# LightGateBoard.net
KiCad netlist of a schematic drawn in EAGLE
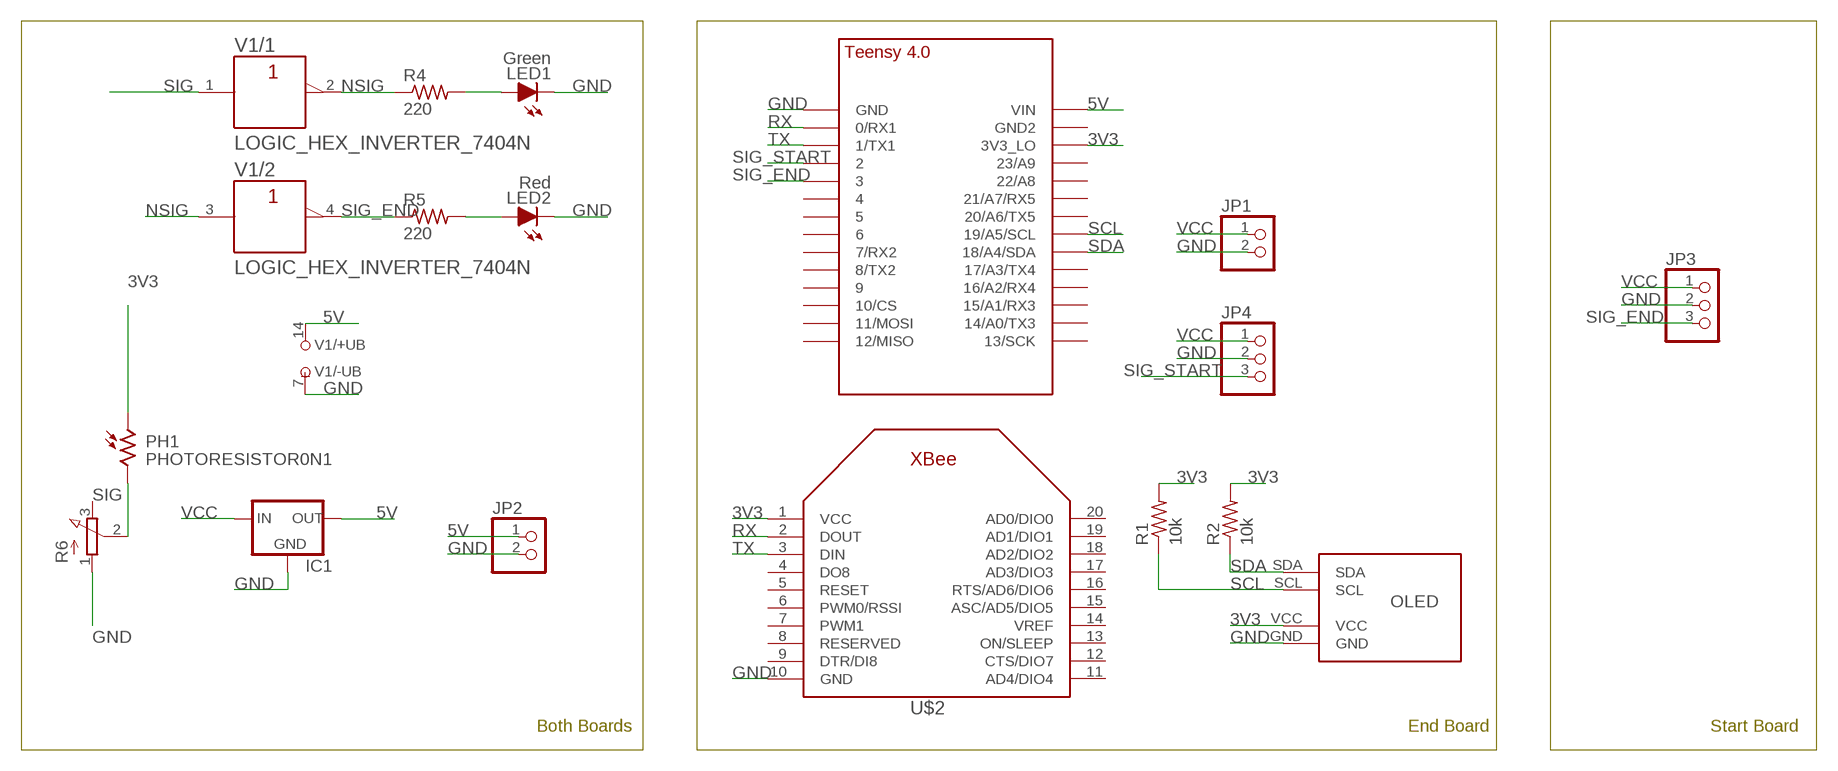
[diagram p0: schematic, sheet 1]

(export (version "E")
  (design (tool "Eeschema 10.0.6"))
  (components
    (comp (ref "IC1")
      (value "REG_5V_L7805_HOR")
      (footprint "eagle-import:TO-220-H")
      (libsource (lib "eagle-import") (part "REG_5V_L7805_HOR"))
    )
    (comp (ref "JP1")
      (value "PINHD-1X2")
      (footprint "eagle-import:1X02")
      (libsource (lib "eagle-import") (part "PINHD-1X2"))
    )
    (comp (ref "JP2")
      (value "PINHD-1X2")
      (footprint "eagle-import:1X02")
      (libsource (lib "eagle-import") (part "PINHD-1X2"))
    )
    (comp (ref "JP3")
      (value "PINHD-1X3")
      (footprint "eagle-import:1X03")
      (libsource (lib "eagle-import") (part "PINHD-1X3"))
    )
    (comp (ref "JP4")
      (value "PINHD-1X3")
      (footprint "eagle-import:1X03")
      (libsource (lib "eagle-import") (part "PINHD-1X3"))
    )
    (comp (ref "LED1")
      (value "Green")
      (footprint "eagle-import:LED-5MM")
      (libsource (lib "eagle-import") (part "LED-5MM"))
    )
    (comp (ref "LED2")
      (value "Red")
      (footprint "eagle-import:LED-5MM")
      (libsource (lib "eagle-import") (part "LED-5MM"))
    )
    (comp (ref "PH1")
      (value "PHOTORESISTOR0N1")
      (footprint "eagle-import:TO46-VT200")
      (libsource (lib "eagle-import") (part "PHOTORESISTOR0N1"))
    )
    (comp (ref "R1")
      (value "10k")
      (footprint "eagle-import:1_4W-0.3")
      (libsource (lib "eagle-import") (part "RES_AXIAL1/4W-0.3"))
    )
    (comp (ref "R2")
      (value "10k")
      (footprint "eagle-import:1_4W-0.3")
      (libsource (lib "eagle-import") (part "RES_AXIAL1/4W-0.3"))
    )
    (comp (ref "R4")
      (value "220")
      (footprint "eagle-import:1_4W-0.3")
      (libsource (lib "eagle-import") (part "RES_AXIAL1/4W-0.3"))
    )
    (comp (ref "R5")
      (value "220")
      (footprint "eagle-import:1_4W-0.3")
      (libsource (lib "eagle-import") (part "RES_AXIAL1/4W-0.3"))
    )
    (comp (ref "R6")
      (value "POTENTIOMETER")
      (footprint "eagle-import:3RP_1610N")
      (libsource (lib "eagle-import") (part "POTENTIOMETER"))
    )
    (comp (ref "U$1")
      (value "TEENSY_4.0_SIMPLE")
      (footprint "eagle-import:TEENSY_4.0_SIMPLE")
      (libsource (lib "eagle-import") (part "TEENSY_4.0_SIMPLE"))
    )
    (comp (ref "U$2")
      (value "XBEE")
      (footprint "eagle-import:XBEE")
      (libsource (lib "eagle-import") (part "XBEE"))
    )
    (comp (ref "U$3")
      (value "OLED_SSD1306")
      (footprint "eagle-import:OLED_SSD1306")
      (libsource (lib "eagle-import") (part "OLED_SSD1306"))
    )
    (comp (ref "V1")
      (value "LOGIC_HEX_INVERTER_7404N")
      (footprint "eagle-import:DIL14")
      (libsource (lib "eagle-import") (part "LOGIC_HEX_INVERTER_7404N"))
    )
  )
  (nets
    (net (code "1") (name "/3V3") (class "Default")
      (node (ref "PH1") (pin "1") (pinfunction "1_1") (pintype "passive"))
      (node (ref "R1") (pin "2") (pinfunction "2_2") (pintype "passive"))
      (node (ref "R2") (pin "2") (pinfunction "2_2") (pintype "passive"))
      (node (ref "U$1") (pin "3V3_LO") (pinfunction "3V3_LO_3V3_LO") (pintype "bidirectional"))
      (node (ref "U$2") (pin "1") (pinfunction "VCC_1") (pintype "power_in"))
      (node (ref "U$3") (pin "VCC") (pinfunction "VCC_VCC") (pintype "bidirectional"))
    )
    (net (code "2") (name "/5V") (class "Default")
      (node (ref "IC1") (pin "3") (pinfunction "OUT_3") (pintype "output"))
      (node (ref "JP2") (pin "1") (pinfunction "1_1") (pintype "passive"))
      (node (ref "U$1") (pin "VIN") (pinfunction "VIN_VIN") (pintype "bidirectional"))
      (node (ref "V1") (pin "14") (pinfunction "+UB_14") (pintype "power_in"))
    )
    (net (code "3") (name "/GND") (class "Default")
      (node (ref "IC1") (pin "2") (pinfunction "GND_2") (pintype "input"))
      (node (ref "JP1") (pin "2") (pinfunction "2_2") (pintype "passive"))
      (node (ref "JP2") (pin "2") (pinfunction "2_2") (pintype "passive"))
      (node (ref "JP3") (pin "2") (pinfunction "2_2") (pintype "passive"))
      (node (ref "JP4") (pin "2") (pinfunction "2_2") (pintype "passive"))
      (node (ref "LED1") (pin "K") (pinfunction "C_K") (pintype "passive"))
      (node (ref "LED2") (pin "K") (pinfunction "C_K") (pintype "passive"))
      (node (ref "R6") (pin "1") (pinfunction "A_1") (pintype "passive"))
      (node (ref "U$1") (pin "GND") (pinfunction "GND_GND") (pintype "bidirectional"))
      (node (ref "U$2") (pin "10") (pinfunction "GND_10") (pintype "power_in"))
      (node (ref "U$3") (pin "GND") (pinfunction "GND_GND") (pintype "bidirectional"))
      (node (ref "V1") (pin "7") (pinfunction "-UB_7") (pintype "power_in"))
    )
    (net (code "4") (name "/NSIG") (class "Default")
      (node (ref "R4") (pin "1") (pinfunction "1_1") (pintype "passive"))
      (node (ref "V1") (pin "2") (pinfunction "Y_2") (pintype "output"))
      (node (ref "V1") (pin "3") (pinfunction "A_3") (pintype "input"))
    )
    (net (code "5") (name "/RX") (class "Default")
      (node (ref "U$1") (pin "0/RX") (pinfunction "0/RX1_0/RX") (pintype "bidirectional"))
      (node (ref "U$2") (pin "2") (pinfunction "DOUT_2") (pintype "output"))
    )
    (net (code "6") (name "/SCL") (class "Default")
      (node (ref "R1") (pin "1") (pinfunction "1_1") (pintype "passive"))
      (node (ref "U$1") (pin "19/A5/SCL") (pinfunction "19/A5/SCL_19/A5/SCL") (pintype "bidirectional"))
      (node (ref "U$3") (pin "SCL") (pinfunction "SCL_SCL") (pintype "bidirectional"))
    )
    (net (code "7") (name "/SDA") (class "Default")
      (node (ref "R2") (pin "1") (pinfunction "1_1") (pintype "passive"))
      (node (ref "U$1") (pin "18/A4/SDA") (pinfunction "18/A4/SDA_18/A4/SDA") (pintype "bidirectional"))
      (node (ref "U$3") (pin "SDA") (pinfunction "SDA_SDA") (pintype "bidirectional"))
    )
    (net (code "8") (name "/SIG") (class "Default")
      (node (ref "PH1") (pin "2") (pinfunction "2_2") (pintype "passive"))
      (node (ref "R6") (pin "2") (pinfunction "S_2") (pintype "passive"))
      (node (ref "V1") (pin "1") (pinfunction "A_1") (pintype "input"))
    )
    (net (code "9") (name "/SIG_END") (class "Default")
      (node (ref "JP3") (pin "3") (pinfunction "3_3") (pintype "passive"))
      (node (ref "R5") (pin "1") (pinfunction "1_1") (pintype "passive"))
      (node (ref "U$1") (pin "3/CANTX") (pinfunction "3_3/CANTX") (pintype "bidirectional"))
      (node (ref "V1") (pin "4") (pinfunction "Y_4") (pintype "output"))
    )
    (net (code "10") (name "/SIG_START") (class "Default")
      (node (ref "JP4") (pin "3") (pinfunction "3_3") (pintype "passive"))
      (node (ref "U$1") (pin "2") (pinfunction "2_2") (pintype "bidirectional"))
    )
    (net (code "11") (name "/TX") (class "Default")
      (node (ref "U$1") (pin "1/TX") (pinfunction "1/TX1_1/TX") (pintype "bidirectional"))
      (node (ref "U$2") (pin "3") (pinfunction "DIN_3") (pintype "input"))
    )
    (net (code "12") (name "/VCC") (class "Default")
      (node (ref "IC1") (pin "1") (pinfunction "IN_1") (pintype "input"))
      (node (ref "JP1") (pin "1") (pinfunction "1_1") (pintype "passive"))
      (node (ref "JP3") (pin "1") (pinfunction "1_1") (pintype "passive"))
      (node (ref "JP4") (pin "1") (pinfunction "1_1") (pintype "passive"))
    )
    (net (code "13") (name "Net-(LED1-PadA)") (class "Default")
      (node (ref "LED1") (pin "A") (pinfunction "A_A") (pintype "passive"))
      (node (ref "R4") (pin "2") (pinfunction "2_2") (pintype "passive"))
    )
    (net (code "14") (name "Net-(LED2-PadA)") (class "Default")
      (node (ref "LED2") (pin "A") (pinfunction "A_A") (pintype "passive"))
      (node (ref "R5") (pin "2") (pinfunction "2_2") (pintype "passive"))
    )
    (net (code "15") (name "unconnected-(R6-E-Pad3)") (class "Default")
      (node (ref "R6") (pin "3") (pinfunction "E_3") (pintype "passive"))
    )
    (net (code "16") (name "unconnected-(U$1-4-Pad4{slash}CANRX)") (class "Default")
      (node (ref "U$1") (pin "4/CANRX") (pinfunction "4_4/CANRX") (pintype "bidirectional"))
    )
    (net (code "17") (name "unconnected-(U$1-7{slash}RX2-Pad7)") (class "Default")
      (node (ref "U$1") (pin "7") (pinfunction "7/RX2_7") (pintype "bidirectional"))
    )
    (net (code "18") (name "unconnected-(U$1-8{slash}TX2-Pad8)") (class "Default")
      (node (ref "U$1") (pin "8") (pinfunction "8/TX2_8") (pintype "bidirectional"))
    )
    (net (code "19") (name "unconnected-(U$1-9-Pad9{slash}CS)") (class "Default")
      (node (ref "U$1") (pin "9/CS") (pinfunction "9_9/CS") (pintype "bidirectional"))
    )
    (net (code "20") (name "unconnected-(U$1-14{slash}A0{slash}TX3-Pad14{slash}A0)") (class "Default")
      (node (ref "U$1") (pin "14/A0") (pinfunction "14/A0/TX3_14/A0") (pintype "bidirectional"))
    )
    (net (code "21") (name "unconnected-(U$1-15{slash}A1{slash}RX3-Pad15{slash}A1)") (class "Default")
      (node (ref "U$1") (pin "15/A1") (pinfunction "15/A1/RX3_15/A1") (pintype "bidirectional"))
    )
    (net (code "22") (name "unconnected-(U$1-16{slash}A2{slash}RX4-Pad16{slash}A2)") (class "Default")
      (node (ref "U$1") (pin "16/A2") (pinfunction "16/A2/RX4_16/A2") (pintype "bidirectional"))
    )
    (net (code "23") (name "unconnected-(U$1-17{slash}A3{slash}TX4-Pad17{slash}A3)") (class "Default")
      (node (ref "U$1") (pin "17/A3") (pinfunction "17/A3/TX4_17/A3") (pintype "bidirectional"))
    )
    (net (code "24") (name "unconnected-(U$1-20{slash}A6{slash}TX5-Pad20{slash}A6)") (class "Default")
      (node (ref "U$1") (pin "20/A6") (pinfunction "20/A6/TX5_20/A6") (pintype "bidirectional"))
    )
    (net (code "25") (name "unconnected-(U$1-21{slash}A7{slash}RX5-Pad21{slash}A7)") (class "Default")
      (node (ref "U$1") (pin "21/A7") (pinfunction "21/A7/RX5_21/A7") (pintype "bidirectional"))
    )
    (net (code "26") (name "unconnected-(U$1-Pad5)") (class "Default")
      (node (ref "U$1") (pin "5") (pinfunction "5_5") (pintype "bidirectional"))
    )
    (net (code "27") (name "unconnected-(U$1-Pad6)") (class "Default")
      (node (ref "U$1") (pin "6") (pinfunction "6_6") (pintype "bidirectional"))
    )
    (net (code "28") (name "unconnected-(U$1-Pad10{slash}CS)") (class "Default")
      (node (ref "U$1") (pin "10/CS") (pinfunction "10/CS_10/CS") (pintype "bidirectional"))
    )
    (net (code "29") (name "unconnected-(U$1-Pad11{slash}MOSI)") (class "Default")
      (node (ref "U$1") (pin "11/MOSI") (pinfunction "11/MOSI_11/MOSI") (pintype "bidirectional"))
    )
    (net (code "30") (name "unconnected-(U$1-Pad12{slash}MISO)") (class "Default")
      (node (ref "U$1") (pin "12/MISO") (pinfunction "12/MISO_12/MISO") (pintype "bidirectional"))
    )
    (net (code "31") (name "unconnected-(U$1-Pad13{slash}SCK)") (class "Default")
      (node (ref "U$1") (pin "13/SCK") (pinfunction "13/SCK_13/SCK") (pintype "bidirectional"))
    )
    (net (code "32") (name "unconnected-(U$1-Pad22{slash}A8)") (class "Default")
      (node (ref "U$1") (pin "22/A8") (pinfunction "22/A8_22/A8") (pintype "bidirectional"))
    )
    (net (code "33") (name "unconnected-(U$1-Pad23{slash}A9)") (class "Default")
      (node (ref "U$1") (pin "23/A9") (pinfunction "23/A9_23/A9") (pintype "bidirectional"))
    )
    (net (code "34") (name "unconnected-(U$1-PadGND2)") (class "Default")
      (node (ref "U$1") (pin "GND2") (pinfunction "GND2_GND2") (pintype "bidirectional"))
    )
    (net (code "35") (name "unconnected-(U$2-AD0{slash}DIO0-Pad20)") (class "Default")
      (node (ref "U$2") (pin "20") (pinfunction "AD0/DIO0_20") (pintype "bidirectional"))
    )
    (net (code "36") (name "unconnected-(U$2-AD1{slash}DIO1-Pad19)") (class "Default")
      (node (ref "U$2") (pin "19") (pinfunction "AD1/DIO1_19") (pintype "bidirectional"))
    )
    (net (code "37") (name "unconnected-(U$2-AD2{slash}DIO2-Pad18)") (class "Default")
      (node (ref "U$2") (pin "18") (pinfunction "AD2/DIO2_18") (pintype "bidirectional"))
    )
    (net (code "38") (name "unconnected-(U$2-AD3{slash}DIO3-Pad17)") (class "Default")
      (node (ref "U$2") (pin "17") (pinfunction "AD3/DIO3_17") (pintype "bidirectional"))
    )
    (net (code "39") (name "unconnected-(U$2-AD4{slash}DIO4-Pad11)") (class "Default")
      (node (ref "U$2") (pin "11") (pinfunction "AD4/DIO4_11") (pintype "bidirectional"))
    )
    (net (code "40") (name "unconnected-(U$2-ASC{slash}AD5{slash}DIO5-Pad15)") (class "Default")
      (node (ref "U$2") (pin "15") (pinfunction "ASC/AD5/DIO5_15") (pintype "bidirectional"))
    )
    (net (code "41") (name "unconnected-(U$2-CTS{slash}DIO7-Pad12)") (class "Default")
      (node (ref "U$2") (pin "12") (pinfunction "CTS/DIO7_12") (pintype "bidirectional"))
    )
    (net (code "42") (name "unconnected-(U$2-DO8-Pad4)") (class "Default")
      (node (ref "U$2") (pin "4") (pinfunction "DO8_4") (pintype "output"))
    )
    (net (code "43") (name "unconnected-(U$2-DTR{slash}DI8-Pad9)") (class "Default")
      (node (ref "U$2") (pin "9") (pinfunction "DTR/DI8_9") (pintype "input"))
    )
    (net (code "44") (name "unconnected-(U$2-ON{slash}SLEEP-Pad13)") (class "Default")
      (node (ref "U$2") (pin "13") (pinfunction "ON/SLEEP_13") (pintype "output"))
    )
    (net (code "45") (name "unconnected-(U$2-PWM0{slash}RSSI-Pad6)") (class "Default")
      (node (ref "U$2") (pin "6") (pinfunction "PWM0/RSSI_6") (pintype "output"))
    )
    (net (code "46") (name "unconnected-(U$2-PWM1-Pad7)") (class "Default")
      (node (ref "U$2") (pin "7") (pinfunction "PWM1_7") (pintype "output"))
    )
    (net (code "47") (name "unconnected-(U$2-RESERVED-Pad8)") (class "Default")
      (node (ref "U$2") (pin "8") (pinfunction "RESERVED_8") (pintype "no_connect"))
    )
    (net (code "48") (name "unconnected-(U$2-RESET-Pad5)") (class "Default")
      (node (ref "U$2") (pin "5") (pinfunction "RESET_5") (pintype "input"))
    )
    (net (code "49") (name "unconnected-(U$2-RTS{slash}AD6{slash}DIO6-Pad16)") (class "Default")
      (node (ref "U$2") (pin "16") (pinfunction "RTS/AD6/DIO6_16") (pintype "bidirectional"))
    )
    (net (code "50") (name "unconnected-(U$2-VREF-Pad14)") (class "Default")
      (node (ref "U$2") (pin "14") (pinfunction "VREF_14") (pintype "input"))
    )
  )
)
